# ONSEMI_MC14504BDR2G.net
KiCad netlist of a schematic drawn in Altium Designer
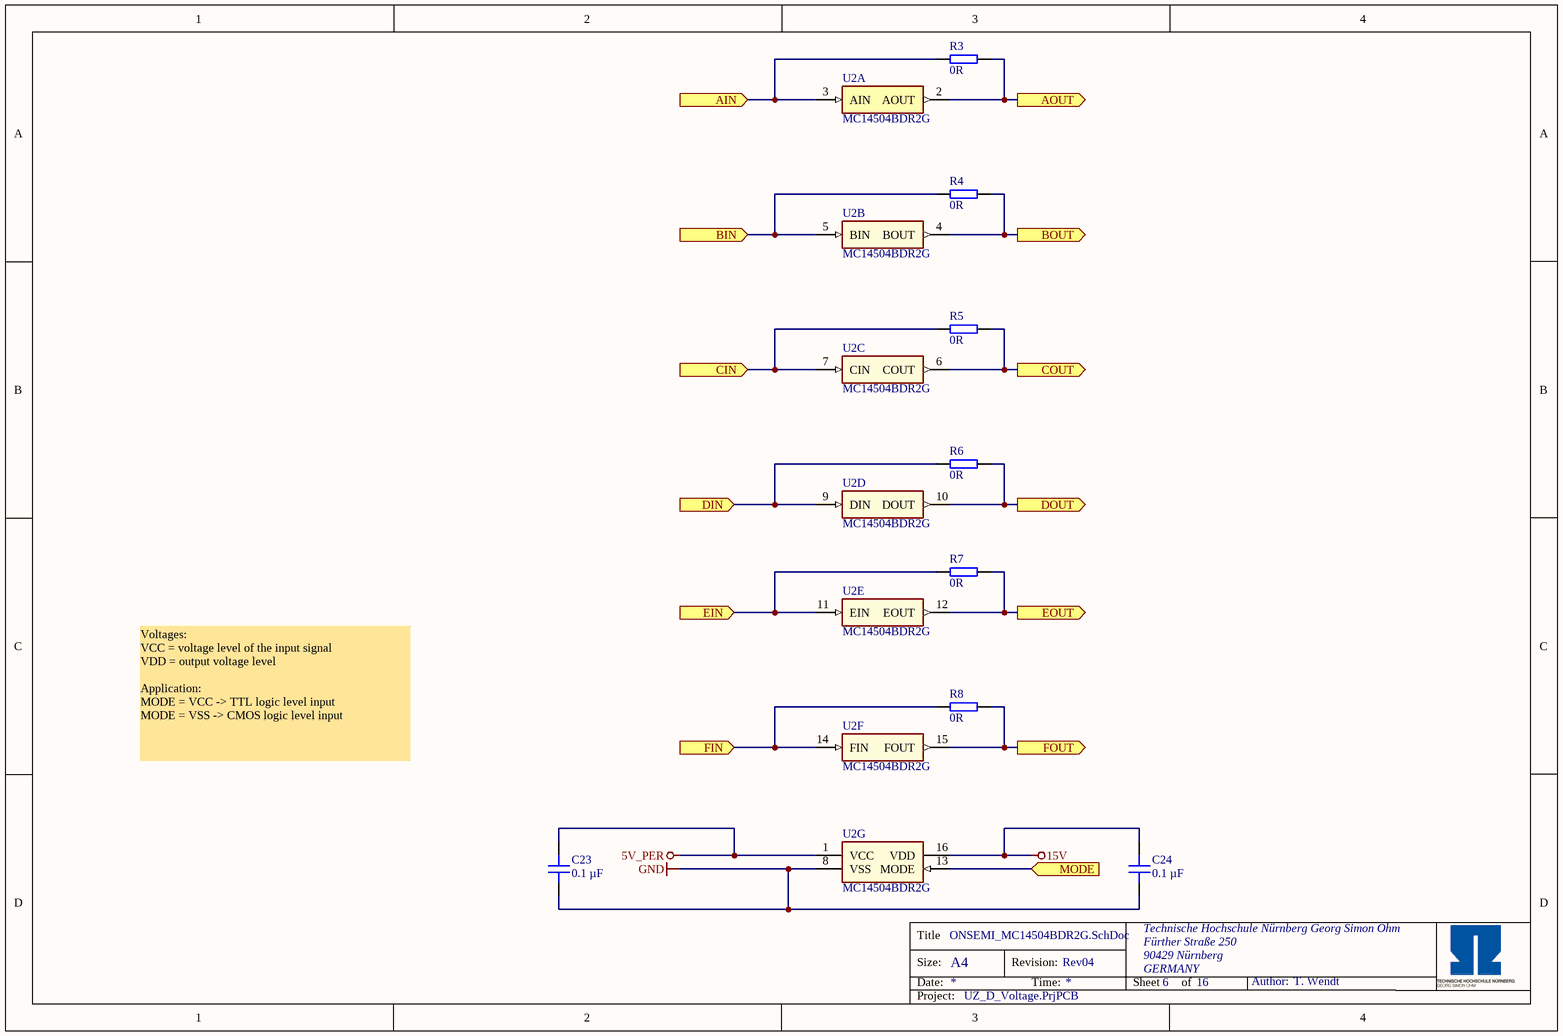
[diagram p0: ONSEMI_MC14504BDR2G.SchDoc]

(export (version "E")
  (design (tool "Eeschema 10.0.6"))
  (components
    (comp (ref "C23")
      (value "0.1 µF")
      (footprint "C_0603")
      (description "Capacitor 0603, 50 VDC, 0.1 µF, X7R")
      (fields
        (field (name "MANUFACTURER PART NUMBER") "C0603X104K5RAC7411")
        (field (name "MANUFACTURER") "KEMET")
        (field (name "CREATED FROM") "MGremer")
      )
      (libsource (lib "user") (part "Capacitor"))
    )
    (comp (ref "C24")
      (value "0.1 µF")
      (footprint "C_0603")
      (description "Capacitor 0603, 50 VDC, 0.1 µF, X7R")
      (fields
        (field (name "MANUFACTURER PART NUMBER") "C0603X104K5RAC7411")
        (field (name "MANUFACTURER") "KEMET")
        (field (name "CREATED FROM") "MGremer")
      )
      (libsource (lib "user") (part "Capacitor"))
    )
    (comp (ref "R3")
      (value "0R")
      (footprint "RES 0603_1608 NO TO")
      (description "SMD resistor E24 series")
      (fields
        (field (name "MANUFACTURER PART NUMBER") "RC0603JR-070RL")
        (field (name "MANUFACTURER") "YAGEO")
        (field (name "CREATED FROM") "MGremer")
      )
      (libsource (lib "user") (part "Resistor"))
    )
    (comp (ref "R4")
      (value "0R")
      (footprint "RES 0603_1608 NO TO")
      (description "SMD resistor E24 series")
      (fields
        (field (name "MANUFACTURER PART NUMBER") "RC0603JR-070RL")
        (field (name "MANUFACTURER") "YAGEO")
        (field (name "CREATED FROM") "MGremer")
      )
      (libsource (lib "user") (part "Resistor"))
    )
    (comp (ref "R5")
      (value "0R")
      (footprint "RES 0603_1608 NO TO")
      (description "SMD resistor E24 series")
      (fields
        (field (name "MANUFACTURER PART NUMBER") "RC0603JR-070RL")
        (field (name "MANUFACTURER") "YAGEO")
        (field (name "CREATED FROM") "MGremer")
      )
      (libsource (lib "user") (part "Resistor"))
    )
    (comp (ref "R6")
      (value "0R")
      (footprint "RES 0603_1608 NO TO")
      (description "SMD resistor E24 series")
      (fields
        (field (name "MANUFACTURER PART NUMBER") "RC0603JR-070RL")
        (field (name "MANUFACTURER") "YAGEO")
        (field (name "CREATED FROM") "MGremer")
      )
      (libsource (lib "user") (part "Resistor"))
    )
    (comp (ref "R7")
      (value "0R")
      (footprint "RES 0603_1608 NO TO")
      (description "SMD resistor E24 series")
      (fields
        (field (name "MANUFACTURER PART NUMBER") "RC0603JR-070RL")
        (field (name "MANUFACTURER") "YAGEO")
        (field (name "CREATED FROM") "MGremer")
      )
      (libsource (lib "user") (part "Resistor"))
    )
    (comp (ref "R8")
      (value "0R")
      (footprint "RES 0603_1608 NO TO")
      (description "SMD resistor E24 series")
      (fields
        (field (name "MANUFACTURER PART NUMBER") "RC0603JR-070RL")
        (field (name "MANUFACTURER") "YAGEO")
        (field (name "CREATED FROM") "MGremer")
      )
      (libsource (lib "user") (part "Resistor"))
    )
    (comp (ref "U2")
      (value "MC14504BDR2G")
      (footprint "SOIC127P600X175-16N")
      (description "Hex Level Shifter for TTL to CMOS or CMOS to CMOS")
      (fields
        (field (name "MANUFACTURER") "ON Semiconductor")
        (field (name "LCSC PART NUMBER") "C7291")
        (field (name "CREATED FROM") "MGremer")
      )
      (libsource (lib "user") (part "MC14504BDR2G"))
    )
  )
  (nets
    (net (code "1") (name "/AIN") (class "Default")
      (node (ref "R3") (pin "1") (pinfunction "1_1") (pintype "passive"))
      (node (ref "U2") (pin "3") (pinfunction "AIN_3") (pintype "input"))
    )
    (net (code "2") (name "/AOUT") (class "Default")
      (node (ref "R3") (pin "2") (pinfunction "2_2") (pintype "passive"))
      (node (ref "U2") (pin "2") (pinfunction "AOUT_2") (pintype "output"))
    )
    (net (code "3") (name "/BIN") (class "Default")
      (node (ref "R4") (pin "1") (pinfunction "1_1") (pintype "passive"))
      (node (ref "U2") (pin "5") (pinfunction "BIN_5") (pintype "input"))
    )
    (net (code "4") (name "/BOUT") (class "Default")
      (node (ref "R4") (pin "2") (pinfunction "2_2") (pintype "passive"))
      (node (ref "U2") (pin "4") (pinfunction "BOUT_4") (pintype "output"))
    )
    (net (code "5") (name "/CIN") (class "Default")
      (node (ref "R5") (pin "1") (pinfunction "1_1") (pintype "passive"))
      (node (ref "U2") (pin "7") (pinfunction "CIN_7") (pintype "input"))
    )
    (net (code "6") (name "/COUT") (class "Default")
      (node (ref "R5") (pin "2") (pinfunction "2_2") (pintype "passive"))
      (node (ref "U2") (pin "6") (pinfunction "COUT_6") (pintype "output"))
    )
    (net (code "7") (name "/DIN") (class "Default")
      (node (ref "R6") (pin "1") (pinfunction "1_1") (pintype "passive"))
      (node (ref "U2") (pin "9") (pinfunction "DIN_9") (pintype "input"))
    )
    (net (code "8") (name "/DOUT") (class "Default")
      (node (ref "R6") (pin "2") (pinfunction "2_2") (pintype "passive"))
      (node (ref "U2") (pin "10") (pinfunction "DOUT_10") (pintype "output"))
    )
    (net (code "9") (name "/EIN") (class "Default")
      (node (ref "R7") (pin "1") (pinfunction "1_1") (pintype "passive"))
      (node (ref "U2") (pin "11") (pinfunction "EIN_11") (pintype "input"))
    )
    (net (code "10") (name "/EOUT") (class "Default")
      (node (ref "R7") (pin "2") (pinfunction "2_2") (pintype "passive"))
      (node (ref "U2") (pin "12") (pinfunction "EOUT_12") (pintype "output"))
    )
    (net (code "11") (name "/FIN") (class "Default")
      (node (ref "R8") (pin "1") (pinfunction "1_1") (pintype "passive"))
      (node (ref "U2") (pin "14") (pinfunction "FIN_14") (pintype "input"))
    )
    (net (code "12") (name "/FOUT") (class "Default")
      (node (ref "R8") (pin "2") (pinfunction "2_2") (pintype "passive"))
      (node (ref "U2") (pin "15") (pinfunction "FOUT_15") (pintype "output"))
    )
    (net (code "13") (name "/MODE") (class "Default")
      (node (ref "U2") (pin "13") (pinfunction "MODE_13") (pintype "input"))
    )
    (net (code "14") (name "5V_PER") (class "Default")
      (node (ref "C23") (pin "2") (pinfunction "2_2") (pintype "passive"))
      (node (ref "U2") (pin "1") (pinfunction "VCC_1") (pintype "power_in"))
    )
    (net (code "15") (name "15V") (class "Default")
      (node (ref "C24") (pin "2") (pinfunction "2_2") (pintype "passive"))
      (node (ref "U2") (pin "16") (pinfunction "VDD_16") (pintype "power_in"))
    )
    (net (code "16") (name "GND") (class "Default")
      (node (ref "C23") (pin "1") (pinfunction "1_1") (pintype "passive"))
      (node (ref "C24") (pin "1") (pinfunction "1_1") (pintype "passive"))
      (node (ref "U2") (pin "8") (pinfunction "VSS_8") (pintype "power_in"))
    )
  )
)
